# Expansion_board.net
KiCad netlist of a schematic drawn in EAGLE
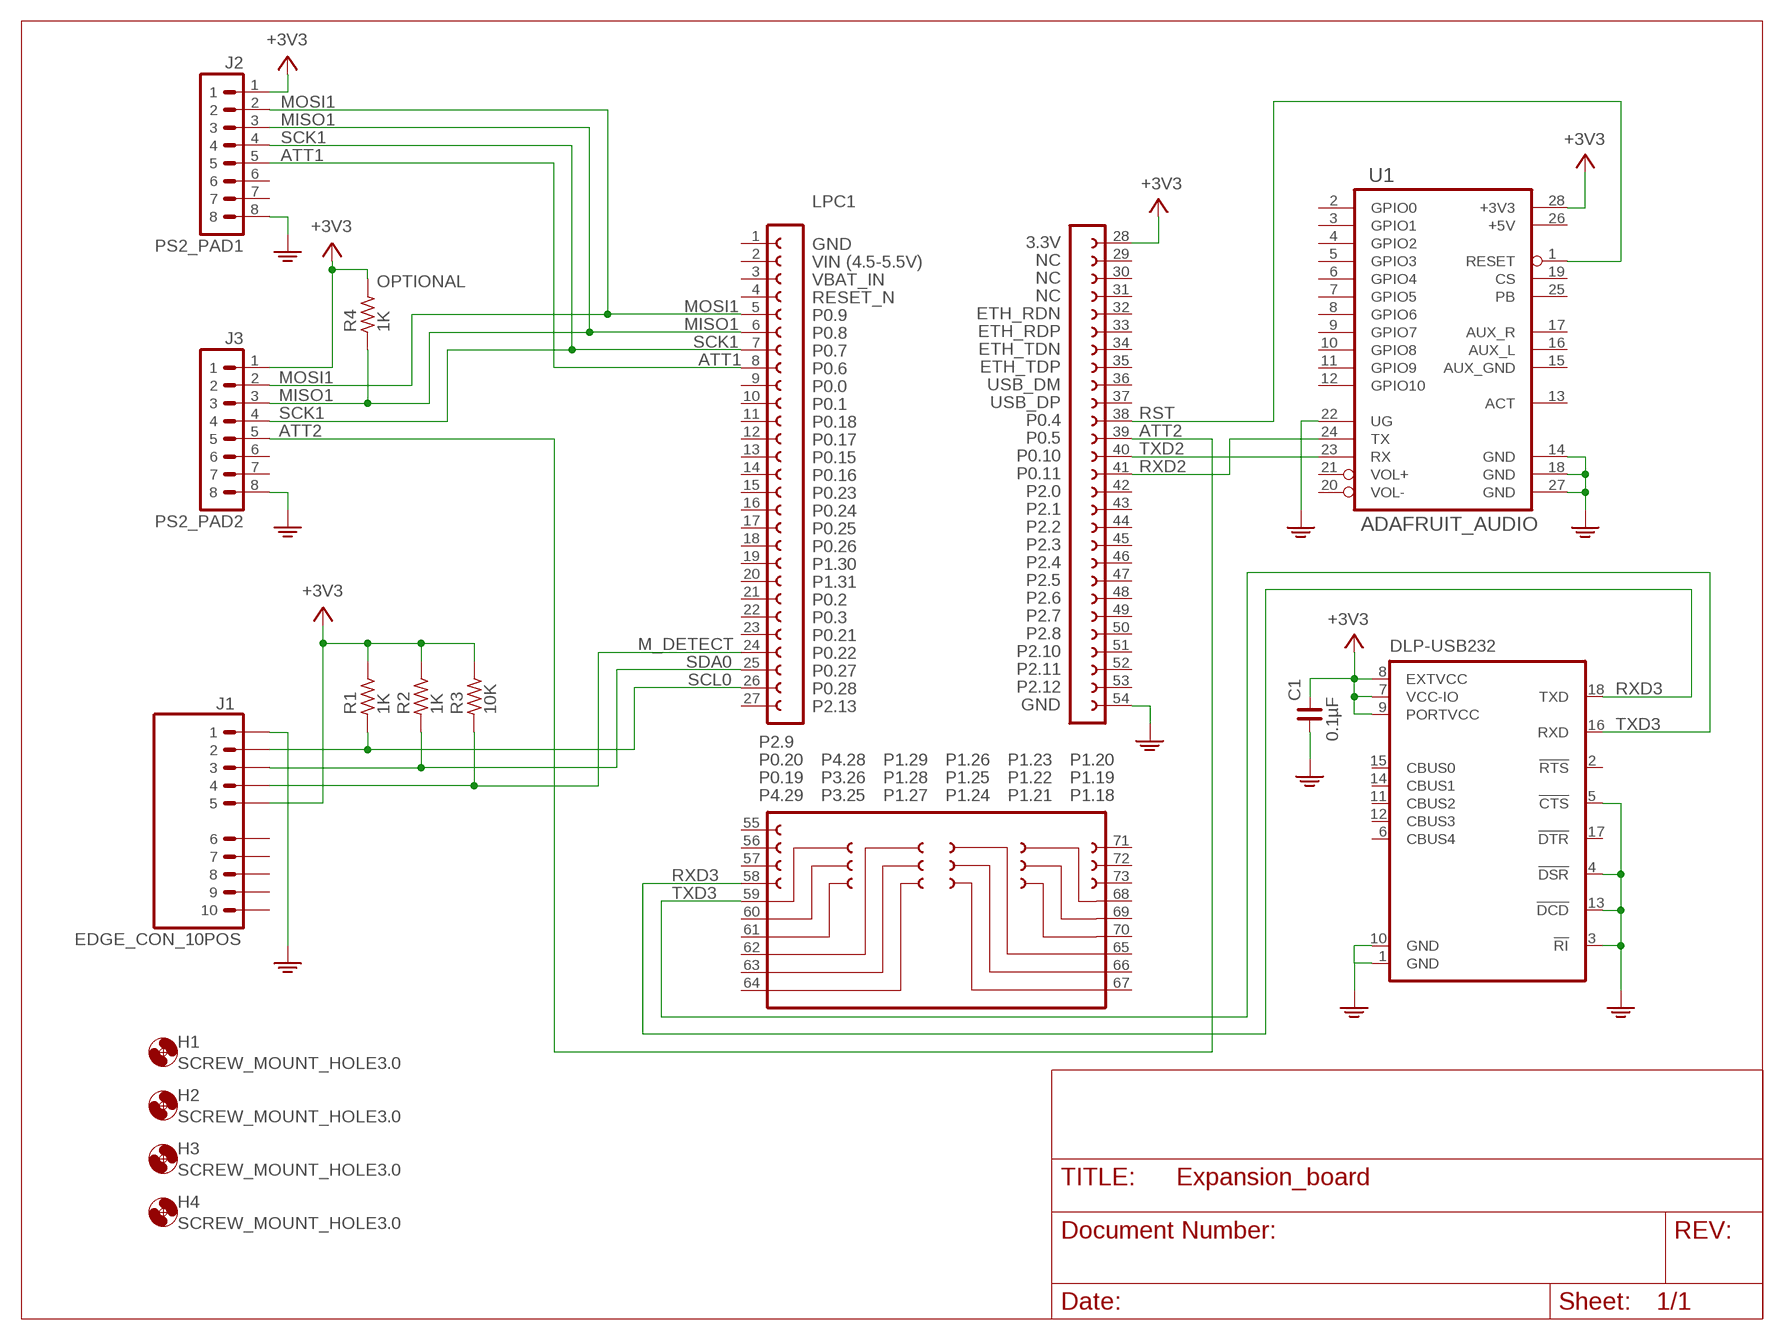
[diagram p0: schematic, sheet 1]

(export (version "E")
  (design (tool "Eeschema 10.0.6"))
  (components
    (comp (ref "C1")
      (value "0.1µF")
      (footprint "eagle-import:C1206")
      (libsource (lib "eagle-import") (part "C_1206"))
    )
    (comp (ref "H1")
      (value "SCREW_MOUNT_HOLE3.0")
      (footprint "eagle-import:3MM_HOLE")
      (libsource (lib "eagle-import") (part "SCREW_MOUNT_HOLE3.0"))
    )
    (comp (ref "H2")
      (value "SCREW_MOUNT_HOLE3.0")
      (footprint "eagle-import:3MM_HOLE")
      (libsource (lib "eagle-import") (part "SCREW_MOUNT_HOLE3.0"))
    )
    (comp (ref "H3")
      (value "SCREW_MOUNT_HOLE3.0")
      (footprint "eagle-import:3MM_HOLE")
      (libsource (lib "eagle-import") (part "SCREW_MOUNT_HOLE3.0"))
    )
    (comp (ref "H4")
      (value "SCREW_MOUNT_HOLE3.0")
      (footprint "eagle-import:3MM_HOLE")
      (libsource (lib "eagle-import") (part "SCREW_MOUNT_HOLE3.0"))
    )
    (comp (ref "J1")
      (value "EDGE_CON_10POS")
      (footprint "eagle-import:EDGE_CON_10POS")
      (libsource (lib "eagle-import") (part "EDGE_CON_10POS"))
    )
    (comp (ref "J2")
      (value "PS2_PAD1")
      (footprint "eagle-import:MOLEX43045_0806")
      (libsource (lib "eagle-import") (part "MOLEX_CON_8POSSMD_43045_0807"))
    )
    (comp (ref "J3")
      (value "PS2_PAD2")
      (footprint "eagle-import:MOLEX43045_0806")
      (libsource (lib "eagle-import") (part "MOLEX_CON_8POSSMD_43045_0807"))
    )
    (comp (ref "LPC1")
      (value "LPCXPRESSO_LPC1769")
      (footprint "eagle-import:LPCXPRESSO_LPC1769")
      (libsource (lib "eagle-import") (part "LPCXPRESSO_LPC1769"))
    )
    (comp (ref "R1")
      (value "1K")
      (footprint "eagle-import:R1206")
      (libsource (lib "eagle-import") (part "R_1206"))
    )
    (comp (ref "R2")
      (value "1K")
      (footprint "eagle-import:R1206")
      (libsource (lib "eagle-import") (part "R_1206"))
    )
    (comp (ref "R3")
      (value "10K")
      (footprint "eagle-import:R1206")
      (libsource (lib "eagle-import") (part "R_1206"))
    )
    (comp (ref "R4")
      (value "1K")
      (footprint "eagle-import:R1206")
      (libsource (lib "eagle-import") (part "R_1206"))
    )
    (comp (ref "U$1")
      (value "DLP-USB232")
      (footprint "eagle-import:DLP-USB232")
      (libsource (lib "eagle-import") (part "DLP-USB232"))
    )
    (comp (ref "U1")
      (value "ADAFRUIT_AUDIO")
      (footprint "eagle-import:AUDIO_FX_SOUND_BOARD")
      (libsource (lib "eagle-import") (part "ADAFRUIT_AUDIO_FX_SOUND_BOARD"))
    )
  )
  (nets
    (net (code "1") (name "+3V3") (class "Default")
      (node (ref "C1") (pin "2") (pinfunction "2_2") (pintype "passive"))
      (node (ref "J1") (pin "5") (pinfunction "5_5") (pintype "passive"))
      (node (ref "J2") (pin "1") (pinfunction "1_1") (pintype "passive"))
      (node (ref "J3") (pin "1") (pinfunction "1_1") (pintype "passive"))
      (node (ref "LPC1") (pin "28") (pinfunction "28_28") (pintype "passive"))
      (node (ref "R1") (pin "2") (pinfunction "2_2") (pintype "passive"))
      (node (ref "R2") (pin "2") (pinfunction "2_2") (pintype "passive"))
      (node (ref "R3") (pin "2") (pinfunction "2_2") (pintype "passive"))
      (node (ref "R4") (pin "2") (pinfunction "2_2") (pintype "passive"))
      (node (ref "U$1") (pin "7") (pinfunction "VCC-IO_7") (pintype "input"))
      (node (ref "U$1") (pin "8") (pinfunction "EXTVCC_8") (pintype "input"))
      (node (ref "U$1") (pin "9") (pinfunction "PORTVCC_9") (pintype "input"))
      (node (ref "U1") (pin "28") (pinfunction "+3V3_28") (pintype "power_in"))
    )
    (net (code "2") (name "/+5V") (class "Default")
      (node (ref "U1") (pin "26") (pinfunction "+5V_26") (pintype "power_in"))
    )
    (net (code "3") (name "/ATT1") (class "Default")
      (node (ref "J2") (pin "5") (pinfunction "5_5") (pintype "passive"))
      (node (ref "LPC1") (pin "8") (pinfunction "8_8") (pintype "passive"))
    )
    (net (code "4") (name "/ATT2") (class "Default")
      (node (ref "J3") (pin "5") (pinfunction "5_5") (pintype "passive"))
      (node (ref "LPC1") (pin "39") (pinfunction "39_39") (pintype "passive"))
    )
    (net (code "5") (name "/MISO1") (class "Default")
      (node (ref "J2") (pin "3") (pinfunction "3_3") (pintype "passive"))
      (node (ref "J3") (pin "3") (pinfunction "3_3") (pintype "passive"))
      (node (ref "LPC1") (pin "6") (pinfunction "6_6") (pintype "passive"))
      (node (ref "R4") (pin "1") (pinfunction "1_1") (pintype "passive"))
    )
    (net (code "6") (name "/MOSI1") (class "Default")
      (node (ref "J2") (pin "2") (pinfunction "2_2") (pintype "passive"))
      (node (ref "J3") (pin "2") (pinfunction "2_2") (pintype "passive"))
      (node (ref "LPC1") (pin "5") (pinfunction "5_5") (pintype "passive"))
    )
    (net (code "7") (name "/M_DETECT") (class "Default")
      (node (ref "J1") (pin "4") (pinfunction "4_4") (pintype "passive"))
      (node (ref "LPC1") (pin "24") (pinfunction "24_24") (pintype "passive"))
      (node (ref "R3") (pin "1") (pinfunction "1_1") (pintype "passive"))
    )
    (net (code "8") (name "/RST") (class "Default")
      (node (ref "LPC1") (pin "38") (pinfunction "38_38") (pintype "passive"))
      (node (ref "U1") (pin "1") (pinfunction "RESET_1") (pintype "input"))
    )
    (net (code "9") (name "/RXD2") (class "Default")
      (node (ref "LPC1") (pin "41") (pinfunction "41_41") (pintype "passive"))
      (node (ref "U1") (pin "24") (pinfunction "TX_24") (pintype "input"))
    )
    (net (code "10") (name "/RXD3") (class "Default")
      (node (ref "LPC1") (pin "58") (pinfunction "58_58") (pintype "passive"))
      (node (ref "U$1") (pin "18") (pinfunction "TXD_18") (pintype "output"))
    )
    (net (code "11") (name "/SCK1") (class "Default")
      (node (ref "J2") (pin "4") (pinfunction "4_4") (pintype "passive"))
      (node (ref "J3") (pin "4") (pinfunction "4_4") (pintype "passive"))
      (node (ref "LPC1") (pin "7") (pinfunction "7_7") (pintype "passive"))
    )
    (net (code "12") (name "/SCL0") (class "Default")
      (node (ref "J1") (pin "2") (pinfunction "2_2") (pintype "passive"))
      (node (ref "LPC1") (pin "26") (pinfunction "26_26") (pintype "passive"))
      (node (ref "R1") (pin "1") (pinfunction "1_1") (pintype "passive"))
    )
    (net (code "13") (name "/SDA0") (class "Default")
      (node (ref "J1") (pin "3") (pinfunction "3_3") (pintype "passive"))
      (node (ref "LPC1") (pin "25") (pinfunction "25_25") (pintype "passive"))
      (node (ref "R2") (pin "1") (pinfunction "1_1") (pintype "passive"))
    )
    (net (code "14") (name "/TXD2") (class "Default")
      (node (ref "LPC1") (pin "40") (pinfunction "40_40") (pintype "passive"))
      (node (ref "U1") (pin "23") (pinfunction "RX_23") (pintype "input"))
    )
    (net (code "15") (name "/TXD3") (class "Default")
      (node (ref "LPC1") (pin "59") (pinfunction "59_59") (pintype "passive"))
      (node (ref "U$1") (pin "16") (pinfunction "RXD_16") (pintype "input"))
    )
    (net (code "16") (name "GND") (class "Default")
      (node (ref "C1") (pin "1") (pinfunction "1_1") (pintype "passive"))
      (node (ref "J1") (pin "1") (pinfunction "1_1") (pintype "passive"))
      (node (ref "J2") (pin "8") (pinfunction "8_8") (pintype "passive"))
      (node (ref "J3") (pin "8") (pinfunction "8_8") (pintype "passive"))
      (node (ref "LPC1") (pin "54") (pinfunction "54_54") (pintype "passive"))
      (node (ref "U$1") (pin "1") (pinfunction "GND_1") (pintype "input"))
      (node (ref "U$1") (pin "10") (pinfunction "GND_10") (pintype "input"))
      (node (ref "U$1") (pin "13") (pinfunction "~{DCD}_13") (pintype "input"))
      (node (ref "U$1") (pin "3") (pinfunction "~{RI}_3") (pintype "input"))
      (node (ref "U$1") (pin "4") (pinfunction "~{DSR}_4") (pintype "input"))
      (node (ref "U$1") (pin "5") (pinfunction "~{CTS}_5") (pintype "input"))
      (node (ref "U1") (pin "14") (pinfunction "GND_14") (pintype "passive"))
      (node (ref "U1") (pin "18") (pinfunction "GND_18") (pintype "passive"))
      (node (ref "U1") (pin "22") (pinfunction "UG_22") (pintype "input"))
      (node (ref "U1") (pin "27") (pinfunction "GND_27") (pintype "passive"))
    )
    (net (code "17") (name "unconnected-(J1-Pad6)") (class "Default")
      (node (ref "J1") (pin "6") (pinfunction "6_6") (pintype "passive"))
    )
    (net (code "18") (name "unconnected-(J1-Pad7)") (class "Default")
      (node (ref "J1") (pin "7") (pinfunction "7_7") (pintype "passive"))
    )
    (net (code "19") (name "unconnected-(J1-Pad8)") (class "Default")
      (node (ref "J1") (pin "8") (pinfunction "8_8") (pintype "passive"))
    )
    (net (code "20") (name "unconnected-(J1-Pad9)") (class "Default")
      (node (ref "J1") (pin "9") (pinfunction "9_9") (pintype "passive"))
    )
    (net (code "21") (name "unconnected-(J1-Pad10)") (class "Default")
      (node (ref "J1") (pin "10") (pinfunction "10_10") (pintype "passive"))
    )
    (net (code "22") (name "unconnected-(J2-Pad6)") (class "Default")
      (node (ref "J2") (pin "6") (pinfunction "6_6") (pintype "passive"))
    )
    (net (code "23") (name "unconnected-(J2-Pad7)") (class "Default")
      (node (ref "J2") (pin "7") (pinfunction "7_7") (pintype "passive"))
    )
    (net (code "24") (name "unconnected-(J3-Pad6)") (class "Default")
      (node (ref "J3") (pin "6") (pinfunction "6_6") (pintype "passive"))
    )
    (net (code "25") (name "unconnected-(J3-Pad7)") (class "Default")
      (node (ref "J3") (pin "7") (pinfunction "7_7") (pintype "passive"))
    )
    (net (code "26") (name "unconnected-(LPC1-Pad1)") (class "Default")
      (node (ref "LPC1") (pin "1") (pinfunction "1_1") (pintype "passive"))
    )
    (net (code "27") (name "unconnected-(LPC1-Pad2)") (class "Default")
      (node (ref "LPC1") (pin "2") (pinfunction "2_2") (pintype "passive"))
    )
    (net (code "28") (name "unconnected-(LPC1-Pad3)") (class "Default")
      (node (ref "LPC1") (pin "3") (pinfunction "3_3") (pintype "passive"))
    )
    (net (code "29") (name "unconnected-(LPC1-Pad4)") (class "Default")
      (node (ref "LPC1") (pin "4") (pinfunction "4_4") (pintype "passive"))
    )
    (net (code "30") (name "unconnected-(LPC1-Pad9)") (class "Default")
      (node (ref "LPC1") (pin "9") (pinfunction "9_9") (pintype "passive"))
    )
    (net (code "31") (name "unconnected-(LPC1-Pad10)") (class "Default")
      (node (ref "LPC1") (pin "10") (pinfunction "10_10") (pintype "passive"))
    )
    (net (code "32") (name "unconnected-(LPC1-Pad11)") (class "Default")
      (node (ref "LPC1") (pin "11") (pinfunction "11_11") (pintype "passive"))
    )
    (net (code "33") (name "unconnected-(LPC1-Pad12)") (class "Default")
      (node (ref "LPC1") (pin "12") (pinfunction "12_12") (pintype "passive"))
    )
    (net (code "34") (name "unconnected-(LPC1-Pad13)") (class "Default")
      (node (ref "LPC1") (pin "13") (pinfunction "13_13") (pintype "passive"))
    )
    (net (code "35") (name "unconnected-(LPC1-Pad14)") (class "Default")
      (node (ref "LPC1") (pin "14") (pinfunction "14_14") (pintype "passive"))
    )
    (net (code "36") (name "unconnected-(LPC1-Pad15)") (class "Default")
      (node (ref "LPC1") (pin "15") (pinfunction "15_15") (pintype "passive"))
    )
    (net (code "37") (name "unconnected-(LPC1-Pad16)") (class "Default")
      (node (ref "LPC1") (pin "16") (pinfunction "16_16") (pintype "passive"))
    )
    (net (code "38") (name "unconnected-(LPC1-Pad17)") (class "Default")
      (node (ref "LPC1") (pin "17") (pinfunction "17_17") (pintype "passive"))
    )
    (net (code "39") (name "unconnected-(LPC1-Pad18)") (class "Default")
      (node (ref "LPC1") (pin "18") (pinfunction "18_18") (pintype "passive"))
    )
    (net (code "40") (name "unconnected-(LPC1-Pad19)") (class "Default")
      (node (ref "LPC1") (pin "19") (pinfunction "19_19") (pintype "passive"))
    )
    (net (code "41") (name "unconnected-(LPC1-Pad20)") (class "Default")
      (node (ref "LPC1") (pin "20") (pinfunction "20_20") (pintype "passive"))
    )
    (net (code "42") (name "unconnected-(LPC1-Pad21)") (class "Default")
      (node (ref "LPC1") (pin "21") (pinfunction "21_21") (pintype "passive"))
    )
    (net (code "43") (name "unconnected-(LPC1-Pad22)") (class "Default")
      (node (ref "LPC1") (pin "22") (pinfunction "22_22") (pintype "passive"))
    )
    (net (code "44") (name "unconnected-(LPC1-Pad23)") (class "Default")
      (node (ref "LPC1") (pin "23") (pinfunction "23_23") (pintype "passive"))
    )
    (net (code "45") (name "unconnected-(LPC1-Pad27)") (class "Default")
      (node (ref "LPC1") (pin "27") (pinfunction "27_27") (pintype "passive"))
    )
    (net (code "46") (name "unconnected-(LPC1-Pad29)") (class "Default")
      (node (ref "LPC1") (pin "29") (pinfunction "29_29") (pintype "passive"))
    )
    (net (code "47") (name "unconnected-(LPC1-Pad30)") (class "Default")
      (node (ref "LPC1") (pin "30") (pinfunction "30_30") (pintype "passive"))
    )
    (net (code "48") (name "unconnected-(LPC1-Pad31)") (class "Default")
      (node (ref "LPC1") (pin "31") (pinfunction "31_31") (pintype "passive"))
    )
    (net (code "49") (name "unconnected-(LPC1-Pad32)") (class "Default")
      (node (ref "LPC1") (pin "32") (pinfunction "32_32") (pintype "passive"))
    )
    (net (code "50") (name "unconnected-(LPC1-Pad33)") (class "Default")
      (node (ref "LPC1") (pin "33") (pinfunction "33_33") (pintype "passive"))
    )
    (net (code "51") (name "unconnected-(LPC1-Pad34)") (class "Default")
      (node (ref "LPC1") (pin "34") (pinfunction "34_34") (pintype "passive"))
    )
    (net (code "52") (name "unconnected-(LPC1-Pad35)") (class "Default")
      (node (ref "LPC1") (pin "35") (pinfunction "35_35") (pintype "passive"))
    )
    (net (code "53") (name "unconnected-(LPC1-Pad36)") (class "Default")
      (node (ref "LPC1") (pin "36") (pinfunction "36_36") (pintype "passive"))
    )
    (net (code "54") (name "unconnected-(LPC1-Pad37)") (class "Default")
      (node (ref "LPC1") (pin "37") (pinfunction "37_37") (pintype "passive"))
    )
    (net (code "55") (name "unconnected-(LPC1-Pad42)") (class "Default")
      (node (ref "LPC1") (pin "42") (pinfunction "42_42") (pintype "passive"))
    )
    (net (code "56") (name "unconnected-(LPC1-Pad43)") (class "Default")
      (node (ref "LPC1") (pin "43") (pinfunction "43_43") (pintype "passive"))
    )
    (net (code "57") (name "unconnected-(LPC1-Pad44)") (class "Default")
      (node (ref "LPC1") (pin "44") (pinfunction "44_44") (pintype "passive"))
    )
    (net (code "58") (name "unconnected-(LPC1-Pad45)") (class "Default")
      (node (ref "LPC1") (pin "45") (pinfunction "45_45") (pintype "passive"))
    )
    (net (code "59") (name "unconnected-(LPC1-Pad46)") (class "Default")
      (node (ref "LPC1") (pin "46") (pinfunction "46_46") (pintype "passive"))
    )
    (net (code "60") (name "unconnected-(LPC1-Pad47)") (class "Default")
      (node (ref "LPC1") (pin "47") (pinfunction "47_47") (pintype "passive"))
    )
    (net (code "61") (name "unconnected-(LPC1-Pad48)") (class "Default")
      (node (ref "LPC1") (pin "48") (pinfunction "48_48") (pintype "passive"))
    )
    (net (code "62") (name "unconnected-(LPC1-Pad49)") (class "Default")
      (node (ref "LPC1") (pin "49") (pinfunction "49_49") (pintype "passive"))
    )
    (net (code "63") (name "unconnected-(LPC1-Pad50)") (class "Default")
      (node (ref "LPC1") (pin "50") (pinfunction "50_50") (pintype "passive"))
    )
    (net (code "64") (name "unconnected-(LPC1-Pad51)") (class "Default")
      (node (ref "LPC1") (pin "51") (pinfunction "51_51") (pintype "passive"))
    )
    (net (code "65") (name "unconnected-(LPC1-Pad52)") (class "Default")
      (node (ref "LPC1") (pin "52") (pinfunction "52_52") (pintype "passive"))
    )
    (net (code "66") (name "unconnected-(LPC1-Pad53)") (class "Default")
      (node (ref "LPC1") (pin "53") (pinfunction "53_53") (pintype "passive"))
    )
    (net (code "67") (name "unconnected-(LPC1-Pad55)") (class "Default")
      (node (ref "LPC1") (pin "55") (pinfunction "55_55") (pintype "passive"))
    )
    (net (code "68") (name "unconnected-(LPC1-Pad56)") (class "Default")
      (node (ref "LPC1") (pin "56") (pinfunction "56_56") (pintype "passive"))
    )
    (net (code "69") (name "unconnected-(LPC1-Pad57)") (class "Default")
      (node (ref "LPC1") (pin "57") (pinfunction "57_57") (pintype "passive"))
    )
    (net (code "70") (name "unconnected-(LPC1-Pad60)") (class "Default")
      (node (ref "LPC1") (pin "60") (pinfunction "60_60") (pintype "passive"))
    )
    (net (code "71") (name "unconnected-(LPC1-Pad61)") (class "Default")
      (node (ref "LPC1") (pin "61") (pinfunction "61_61") (pintype "passive"))
    )
    (net (code "72") (name "unconnected-(LPC1-Pad62)") (class "Default")
      (node (ref "LPC1") (pin "62") (pinfunction "62_62") (pintype "passive"))
    )
    (net (code "73") (name "unconnected-(LPC1-Pad63)") (class "Default")
      (node (ref "LPC1") (pin "63") (pinfunction "63_63") (pintype "passive"))
    )
    (net (code "74") (name "unconnected-(LPC1-Pad64)") (class "Default")
      (node (ref "LPC1") (pin "64") (pinfunction "64_64") (pintype "passive"))
    )
    (net (code "75") (name "unconnected-(LPC1-Pad65)") (class "Default")
      (node (ref "LPC1") (pin "65") (pinfunction "65_65") (pintype "passive"))
    )
    (net (code "76") (name "unconnected-(LPC1-Pad66)") (class "Default")
      (node (ref "LPC1") (pin "66") (pinfunction "66_66") (pintype "passive"))
    )
    (net (code "77") (name "unconnected-(LPC1-Pad67)") (class "Default")
      (node (ref "LPC1") (pin "67") (pinfunction "67_67") (pintype "passive"))
    )
    (net (code "78") (name "unconnected-(LPC1-Pad68)") (class "Default")
      (node (ref "LPC1") (pin "68") (pinfunction "68_68") (pintype "passive"))
    )
    (net (code "79") (name "unconnected-(LPC1-Pad69)") (class "Default")
      (node (ref "LPC1") (pin "69") (pinfunction "69_69") (pintype "passive"))
    )
    (net (code "80") (name "unconnected-(LPC1-Pad70)") (class "Default")
      (node (ref "LPC1") (pin "70") (pinfunction "70_70") (pintype "passive"))
    )
    (net (code "81") (name "unconnected-(LPC1-Pad71)") (class "Default")
      (node (ref "LPC1") (pin "71") (pinfunction "71_71") (pintype "passive"))
    )
    (net (code "82") (name "unconnected-(LPC1-Pad72)") (class "Default")
      (node (ref "LPC1") (pin "72") (pinfunction "72_72") (pintype "passive"))
    )
    (net (code "83") (name "unconnected-(LPC1-Pad73)") (class "Default")
      (node (ref "LPC1") (pin "73") (pinfunction "73_73") (pintype "passive"))
    )
    (net (code "84") (name "unconnected-(U$1-CBUS0-Pad15)") (class "Default")
      (node (ref "U$1") (pin "15") (pinfunction "CBUS0_15") (pintype "input"))
    )
    (net (code "85") (name "unconnected-(U$1-CBUS1-Pad14)") (class "Default")
      (node (ref "U$1") (pin "14") (pinfunction "CBUS1_14") (pintype "input"))
    )
    (net (code "86") (name "unconnected-(U$1-CBUS2-Pad11)") (class "Default")
      (node (ref "U$1") (pin "11") (pinfunction "CBUS2_11") (pintype "input"))
    )
    (net (code "87") (name "unconnected-(U$1-CBUS3-Pad12)") (class "Default")
      (node (ref "U$1") (pin "12") (pinfunction "CBUS3_12") (pintype "input"))
    )
    (net (code "88") (name "unconnected-(U$1-CBUS4-Pad6)") (class "Default")
      (node (ref "U$1") (pin "6") (pinfunction "CBUS4_6") (pintype "input"))
    )
    (net (code "89") (name "unconnected-(U$1-~{DTR}-Pad17)") (class "Default")
      (node (ref "U$1") (pin "17") (pinfunction "~{DTR}_17") (pintype "input"))
    )
    (net (code "90") (name "unconnected-(U$1-~{RTS}-Pad2)") (class "Default")
      (node (ref "U$1") (pin "2") (pinfunction "~{RTS}_2") (pintype "input"))
    )
    (net (code "91") (name "unconnected-(U1-ACT-Pad13)") (class "Default")
      (node (ref "U1") (pin "13") (pinfunction "ACT_13") (pintype "output"))
    )
    (net (code "92") (name "unconnected-(U1-AUX_GND-Pad15)") (class "Default")
      (node (ref "U1") (pin "15") (pinfunction "AUX_GND_15") (pintype "output"))
    )
    (net (code "93") (name "unconnected-(U1-AUX_L-Pad16)") (class "Default")
      (node (ref "U1") (pin "16") (pinfunction "AUX_L_16") (pintype "output"))
    )
    (net (code "94") (name "unconnected-(U1-AUX_R-Pad17)") (class "Default")
      (node (ref "U1") (pin "17") (pinfunction "AUX_R_17") (pintype "output"))
    )
    (net (code "95") (name "unconnected-(U1-CS-Pad19)") (class "Default")
      (node (ref "U1") (pin "19") (pinfunction "CS_19") (pintype "input"))
    )
    (net (code "96") (name "unconnected-(U1-GPIO0-Pad2)") (class "Default")
      (node (ref "U1") (pin "2") (pinfunction "GPIO0_2") (pintype "input"))
    )
    (net (code "97") (name "unconnected-(U1-GPIO1-Pad3)") (class "Default")
      (node (ref "U1") (pin "3") (pinfunction "GPIO1_3") (pintype "input"))
    )
    (net (code "98") (name "unconnected-(U1-GPIO2-Pad4)") (class "Default")
      (node (ref "U1") (pin "4") (pinfunction "GPIO2_4") (pintype "input"))
    )
    (net (code "99") (name "unconnected-(U1-GPIO3-Pad5)") (class "Default")
      (node (ref "U1") (pin "5") (pinfunction "GPIO3_5") (pintype "input"))
    )
    (net (code "100") (name "unconnected-(U1-GPIO4-Pad6)") (class "Default")
      (node (ref "U1") (pin "6") (pinfunction "GPIO4_6") (pintype "input"))
    )
    (net (code "101") (name "unconnected-(U1-GPIO5-Pad7)") (class "Default")
      (node (ref "U1") (pin "7") (pinfunction "GPIO5_7") (pintype "input"))
    )
    (net (code "102") (name "unconnected-(U1-GPIO6-Pad8)") (class "Default")
      (node (ref "U1") (pin "8") (pinfunction "GPIO6_8") (pintype "input"))
    )
    (net (code "103") (name "unconnected-(U1-GPIO7-Pad9)") (class "Default")
      (node (ref "U1") (pin "9") (pinfunction "GPIO7_9") (pintype "input"))
    )
    (net (code "104") (name "unconnected-(U1-GPIO8-Pad10)") (class "Default")
      (node (ref "U1") (pin "10") (pinfunction "GPIO8_10") (pintype "input"))
    )
    (net (code "105") (name "unconnected-(U1-GPIO9-Pad11)") (class "Default")
      (node (ref "U1") (pin "11") (pinfunction "GPIO9_11") (pintype "input"))
    )
    (net (code "106") (name "unconnected-(U1-GPIO10-Pad12)") (class "Default")
      (node (ref "U1") (pin "12") (pinfunction "GPIO10_12") (pintype "input"))
    )
    (net (code "107") (name "unconnected-(U1-PB-Pad25)") (class "Default")
      (node (ref "U1") (pin "25") (pinfunction "PB_25") (pintype "output"))
    )
    (net (code "108") (name "unconnected-(U1-VOL+-Pad21)") (class "Default")
      (node (ref "U1") (pin "21") (pinfunction "VOL+_21") (pintype "input"))
    )
    (net (code "109") (name "unconnected-(U1-VOL--Pad20)") (class "Default")
      (node (ref "U1") (pin "20") (pinfunction "VOL-_20") (pintype "input"))
    )
  )
)
